# 07_MIPI_CSI.net
KiCad netlist of a schematic drawn in Altium Designer
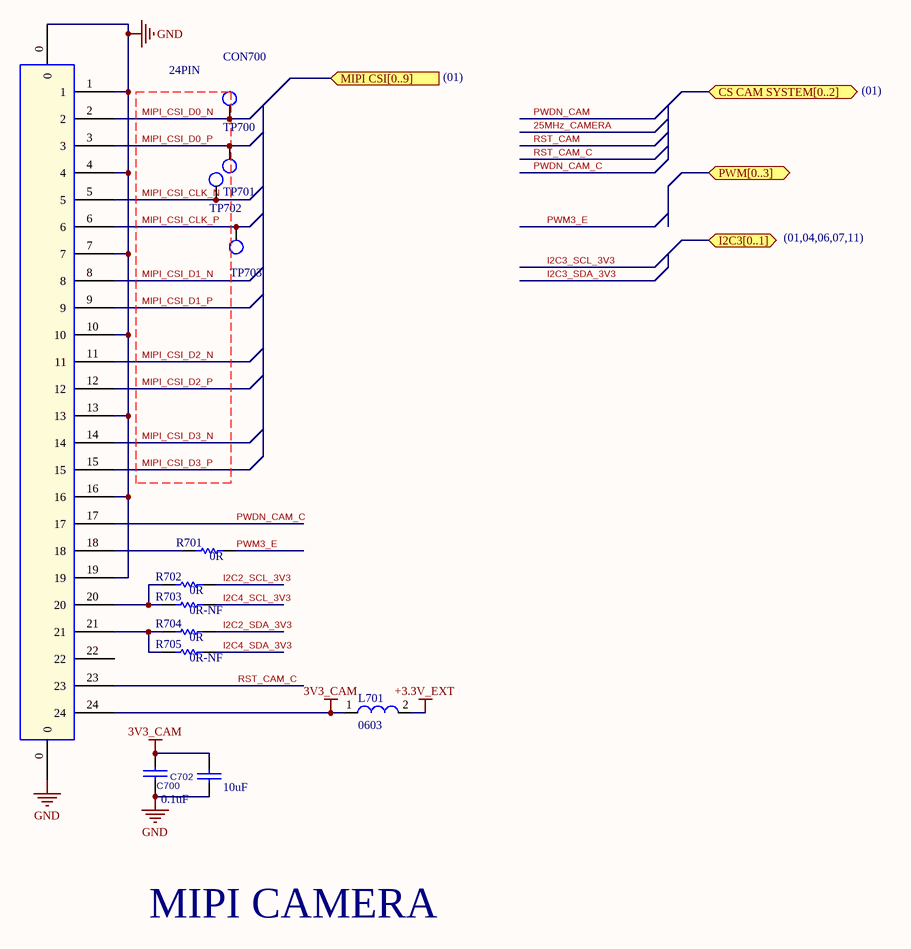
[diagram p0: 07 MIPI CSI.SchDoc]

(export (version "E")
  (design (tool "Eeschema 10.0.6"))
  (components
    (comp (ref "C700")
      (value "0.1uF")
      (footprint "0402_CC")
      (description "CAP VER 0.1UF 16V X7R 0402")
      (fields (field (name "CREATED BY") "LA") (field (name "CHECKED BY") "*"))
      (libsource (lib "ARETE_SCH") (part "CAP-CL05B104KO5NNNC"))
    )
    (comp (ref "C702")
      (value "10uF")
      (footprint "0603_CC")
      (description "CAP CER 10UF 6.3V X6S 0603")
      (fields (field (name "CREATED BY") "LA") (field (name "CHECKED BY") "*"))
      (libsource (lib "ARETE_SCH") (part "CAP-JMK107BC6106MA-T"))
    )
    (comp (ref "CON700")
      (value "24PIN")
      (footprint "24-PIN FPC")
      (description "CONN FPC TOP 24POS 0.50MM R/A")
      (fields (field (name "CREATED BY") "LA") (field (name "CHECKED BY") "*"))
      (libsource (lib "ARETE_SCH") (part "CON-SFV24R-4STBE1HLF(GENIS)"))
    )
    (comp (ref "L701")
      (value "0603")
      (footprint "0603_RES")
      (description "0OHM 0603")
      (fields (field (name "CREATED BY") "EE") (field (name "CHECKED BY") "*"))
      (libsource (lib "ARETE_SCH") (part "IND-FERRITE (RES 0 OHM) 0603"))
    )
    (comp (ref "R701")
      (value "0R")
      (footprint "0402_RES")
      (description "RES 0 OHM JUMPER 1/16W 0402")
      (fields (field (name "CREATED BY") "LA") (field (name "CHECKED BY") "*"))
      (libsource (lib "ARETE_SCH") (part "RES-RMCF0402ZT0R00"))
    )
    (comp (ref "R702")
      (value "0R")
      (footprint "0402_RES")
      (description "RES 0 OHM JUMPER 1/16W 0402")
      (fields (field (name "CREATED BY") "LA") (field (name "CHECKED BY") "*"))
      (libsource (lib "ARETE_SCH") (part "RES-RMCF0402ZT0R00"))
    )
    (comp (ref "R703")
      (value "0R-NF")
      (footprint "0402_RES")
      (description "RES 0 OHM JUMPER 1/16W 0402")
      (fields (field (name "CREATED BY") "LA") (field (name "CHECKED BY") "*"))
      (libsource (lib "ARETE_SCH") (part "RES-RMCF0402ZT0R00"))
    )
    (comp (ref "R704")
      (value "0R")
      (footprint "0402_RES")
      (description "RES 0 OHM JUMPER 1/16W 0402")
      (fields (field (name "CREATED BY") "LA") (field (name "CHECKED BY") "*"))
      (libsource (lib "ARETE_SCH") (part "RES-RMCF0402ZT0R00"))
    )
    (comp (ref "R705")
      (value "0R-NF")
      (footprint "0402_RES")
      (description "RES 0 OHM JUMPER 1/16W 0402")
      (fields (field (name "CREATED BY") "LA") (field (name "CHECKED BY") "*"))
      (libsource (lib "ARETE_SCH") (part "RES-RMCF0402ZT0R00"))
    )
    (comp (ref "TP700")
      (value "TEST POINT 15")
      (footprint "testpoint_15")
      (libsource (lib "ARETE_L") (part "TEST POINT 15"))
    )
    (comp (ref "TP701")
      (value "TEST POINT 15")
      (footprint "testpoint_15")
      (libsource (lib "ARETE_L") (part "TEST POINT 15"))
    )
    (comp (ref "TP702")
      (value "TEST POINT 15")
      (footprint "testpoint_15")
      (libsource (lib "ARETE_L") (part "TEST POINT 15"))
    )
    (comp (ref "TP703")
      (value "TEST POINT 15")
      (footprint "testpoint_15")
      (libsource (lib "ARETE_L") (part "TEST POINT 15"))
    )
  )
  (nets
    (net (code "7") (name "+3.3V_EXT") (class "Default")
      (node (ref "L701") (pin "2") (pinfunction "2_2") (pintype "passive"))
    )
    (net (code "10") (name "/I2C2_SCL_3V3") (class "Default")
      (node (ref "R702") (pin "2") (pinfunction "2_2") (pintype "passive"))
    )
    (net (code "11") (name "/I2C2_SDA_3V3") (class "Default")
      (node (ref "R704") (pin "2") (pinfunction "2_2") (pintype "passive"))
    )
    (net (code "15") (name "/I2C4_SCL_3V3") (class "Default")
      (node (ref "R703") (pin "2") (pinfunction "2_2") (pintype "passive"))
    )
    (net (code "16") (name "/I2C4_SDA_3V3") (class "Default")
      (node (ref "R705") (pin "2") (pinfunction "2_2") (pintype "passive"))
    )
    (net (code "18") (name "/MIPI_CSI_CLK_N") (class "Default")
      (node (ref "CON700") (pin "5") (pinfunction "5_5") (pintype "passive"))
      (node (ref "TP702") (pin "1") (pinfunction "1_1") (pintype "passive"))
    )
    (net (code "19") (name "/MIPI_CSI_CLK_P") (class "Default")
      (node (ref "CON700") (pin "6") (pinfunction "6_6") (pintype "passive"))
      (node (ref "TP703") (pin "1") (pinfunction "1_1") (pintype "passive"))
    )
    (net (code "20") (name "/MIPI_CSI_D0_N") (class "Default")
      (node (ref "CON700") (pin "2") (pinfunction "2_2") (pintype "passive"))
      (node (ref "TP700") (pin "1") (pinfunction "1_1") (pintype "passive"))
    )
    (net (code "21") (name "/MIPI_CSI_D0_P") (class "Default")
      (node (ref "CON700") (pin "3") (pinfunction "3_3") (pintype "passive"))
      (node (ref "TP701") (pin "1") (pinfunction "1_1") (pintype "passive"))
    )
    (net (code "22") (name "/MIPI_CSI_D1_N") (class "Default")
      (node (ref "CON700") (pin "8") (pinfunction "8_8") (pintype "passive"))
    )
    (net (code "23") (name "/MIPI_CSI_D1_P") (class "Default")
      (node (ref "CON700") (pin "9") (pinfunction "9_9") (pintype "passive"))
    )
    (net (code "24") (name "/MIPI_CSI_D2_N") (class "Default")
      (node (ref "CON700") (pin "11") (pinfunction "11_11") (pintype "passive"))
    )
    (net (code "25") (name "/MIPI_CSI_D2_P") (class "Default")
      (node (ref "CON700") (pin "12") (pinfunction "12_12") (pintype "passive"))
    )
    (net (code "26") (name "/MIPI_CSI_D3_N") (class "Default")
      (node (ref "CON700") (pin "14") (pinfunction "14_14") (pintype "passive"))
    )
    (net (code "27") (name "/MIPI_CSI_D3_P") (class "Default")
      (node (ref "CON700") (pin "15") (pinfunction "15_15") (pintype "passive"))
    )
    (net (code "29") (name "/PWDN_CAM_C") (class "Default")
      (node (ref "CON700") (pin "17") (pinfunction "17_17") (pintype "passive"))
    )
    (net (code "30") (name "/PWM3_E") (class "Default")
      (node (ref "R701") (pin "2") (pinfunction "2_2") (pintype "passive"))
    )
    (net (code "33") (name "/RST_CAM_C") (class "Default")
      (node (ref "CON700") (pin "23") (pinfunction "23_23") (pintype "passive"))
    )
    (net (code "34") (name "3V3_CAM") (class "Default")
      (node (ref "C700") (pin "1") (pinfunction "1_1") (pintype "passive"))
      (node (ref "C702") (pin "1") (pinfunction "1_1") (pintype "passive"))
      (node (ref "CON700") (pin "24") (pinfunction "24_24") (pintype "passive"))
      (node (ref "L701") (pin "1") (pinfunction "1_1") (pintype "passive"))
    )
    (net (code "35") (name "GND") (class "Default")
      (node (ref "C700") (pin "2") (pinfunction "2_2") (pintype "passive"))
      (node (ref "C702") (pin "2") (pinfunction "2_2") (pintype "passive"))
      (node (ref "CON700") (pin "0") (pinfunction "0_0") (pintype "passive"))
      (node (ref "CON700") (pin "1") (pinfunction "1_1") (pintype "passive"))
      (node (ref "CON700") (pin "10") (pinfunction "10_10") (pintype "passive"))
      (node (ref "CON700") (pin "13") (pinfunction "13_13") (pintype "passive"))
      (node (ref "CON700") (pin "16") (pinfunction "16_16") (pintype "passive"))
      (node (ref "CON700") (pin "19") (pinfunction "19_19") (pintype "passive"))
      (node (ref "CON700") (pin "4") (pinfunction "4_4") (pintype "passive"))
      (node (ref "CON700") (pin "7") (pinfunction "7_7") (pintype "passive"))
    )
    (net (code "36") (name "Net-(CON700-Pad18)") (class "Default")
      (node (ref "CON700") (pin "18") (pinfunction "18_18") (pintype "passive"))
      (node (ref "R701") (pin "1") (pinfunction "1_1") (pintype "passive"))
    )
    (net (code "37") (name "Net-(CON700-Pad20)") (class "Default")
      (node (ref "CON700") (pin "20") (pinfunction "20_20") (pintype "passive"))
      (node (ref "R702") (pin "1") (pinfunction "1_1") (pintype "passive"))
      (node (ref "R703") (pin "1") (pinfunction "1_1") (pintype "passive"))
    )
    (net (code "38") (name "Net-(CON700-Pad21)") (class "Default")
      (node (ref "CON700") (pin "21") (pinfunction "21_21") (pintype "passive"))
      (node (ref "R704") (pin "1") (pinfunction "1_1") (pintype "passive"))
      (node (ref "R705") (pin "1") (pinfunction "1_1") (pintype "passive"))
    )
    (net (code "39") (name "unconnected-(CON700-Pad22)") (class "Default")
      (node (ref "CON700") (pin "22") (pinfunction "22_22") (pintype "passive"))
    )
  )
)
